# MLS01-TG000-C08.net
KiCad netlist of a schematic drawn in EAGLE
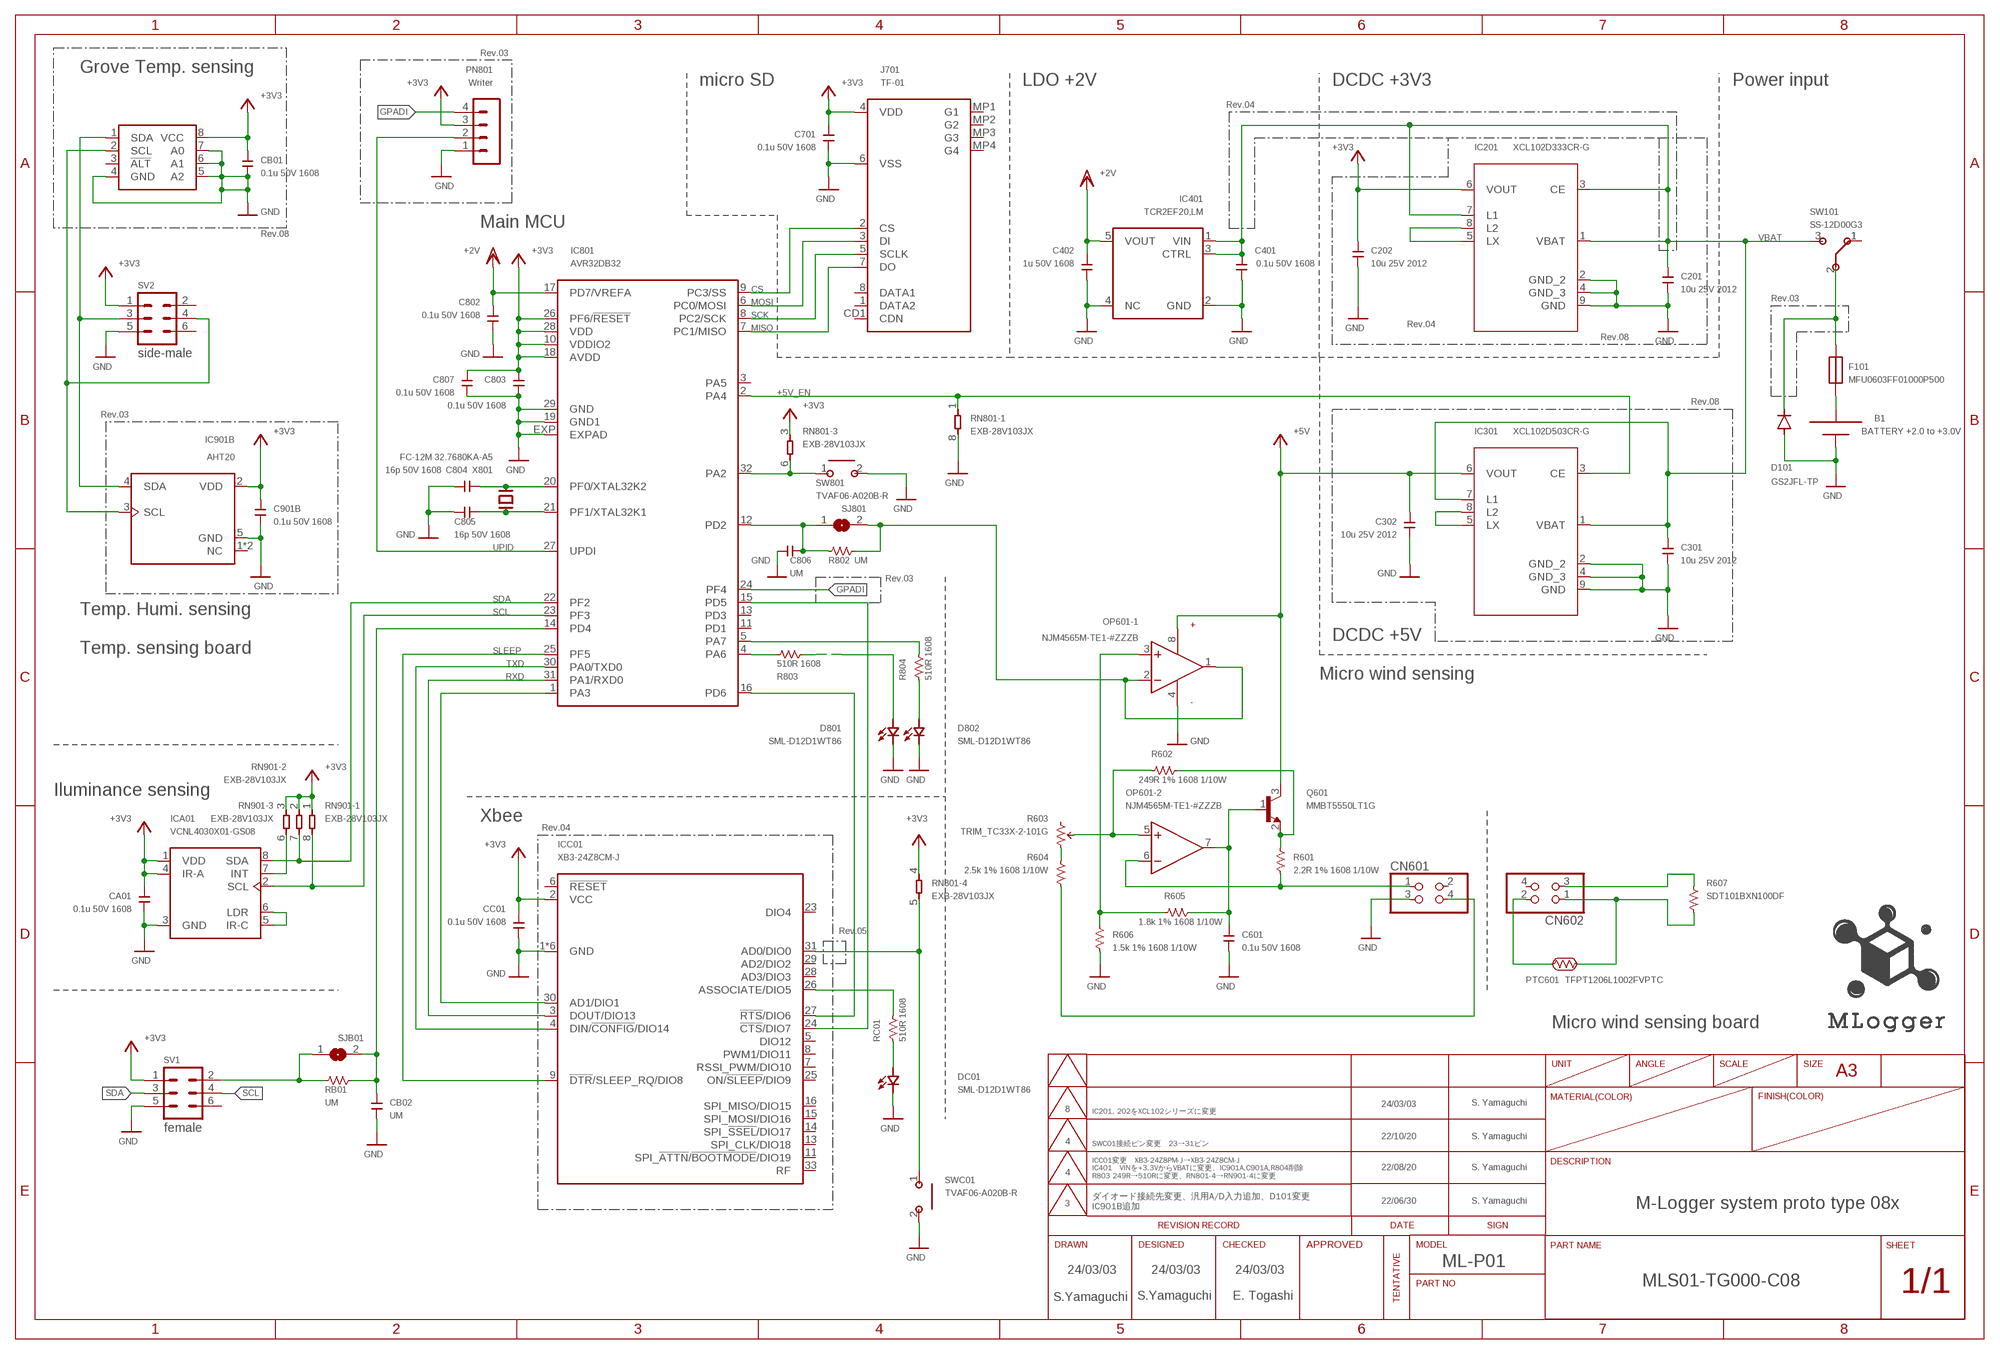
[diagram p0: schematic, sheet 1]

(export (version "E")
  (design (tool "Eeschema 10.0.6"))
  (components
    (comp (ref "B1")
      (value "BATTERY +2.0 to +3.0V")
      (footprint "eagle-import:PAD")
      (libsource (lib "eagle-import") (part "BATTERY"))
    )
    (comp (ref "C201")
      (value "10u 25V 2012")
      (footprint "eagle-import:C-2012_0805")
      (libsource (lib "eagle-import") (part "CL21B105KBFNNNG"))
    )
    (comp (ref "C202")
      (value "10u 25V 2012")
      (footprint "eagle-import:C-2012_0805")
      (libsource (lib "eagle-import") (part "CL21B105KBFNNNG"))
    )
    (comp (ref "C301")
      (value "10u 25V 2012")
      (footprint "eagle-import:C-2012_0805")
      (libsource (lib "eagle-import") (part "CL21B105KBFNNNG"))
    )
    (comp (ref "C302")
      (value "10u 25V 2012")
      (footprint "eagle-import:C-2012_0805")
      (libsource (lib "eagle-import") (part "CL21B105KBFNNNG"))
    )
    (comp (ref "C401")
      (value "0.1u 50V 1608")
      (footprint "eagle-import:C-1608_0603")
      (libsource (lib "eagle-import") (part "CL10A105KP8NNNC"))
    )
    (comp (ref "C402")
      (value "1u 50V 1608")
      (footprint "eagle-import:C-1608_0603")
      (libsource (lib "eagle-import") (part "CL10A105KP8NNNC"))
    )
    (comp (ref "C601")
      (value "0.1u 50V 1608")
      (footprint "eagle-import:C-1608_0603")
      (libsource (lib "eagle-import") (part "CL10A105KP8NNNC"))
    )
    (comp (ref "C701")
      (value "0.1u 50V 1608")
      (footprint "eagle-import:C-1608_0603")
      (libsource (lib "eagle-import") (part "CL10A105KP8NNNC"))
    )
    (comp (ref "C802")
      (value "0.1u 50V 1608")
      (footprint "eagle-import:C-1608_0603")
      (libsource (lib "eagle-import") (part "CL10A105KP8NNNC"))
    )
    (comp (ref "C803")
      (value "0.1u 50V 1608")
      (footprint "eagle-import:C-1608_0603")
      (libsource (lib "eagle-import") (part "CL10A105KP8NNNC"))
    )
    (comp (ref "C804")
      (value "16p 50V 1608")
      (footprint "eagle-import:C-1608_0603")
      (libsource (lib "eagle-import") (part "CL10A105KP8NNNC"))
    )
    (comp (ref "C805")
      (value "16p 50V 1608")
      (footprint "eagle-import:C-1608_0603")
      (libsource (lib "eagle-import") (part "CL10A105KP8NNNC"))
    )
    (comp (ref "C806")
      (value "UM")
      (footprint "eagle-import:C-1608_0603")
      (libsource (lib "eagle-import") (part "CL10A105KP8NNNC"))
    )
    (comp (ref "C807")
      (value "0.1u 50V 1608")
      (footprint "eagle-import:C-1608_0603")
      (libsource (lib "eagle-import") (part "CL10A105KP8NNNC"))
    )
    (comp (ref "C901B")
      (value "0.1u 50V 1608")
      (footprint "eagle-import:C-1608_0603")
      (libsource (lib "eagle-import") (part "CL10A105KP8NNNC"))
    )
    (comp (ref "CA01")
      (value "0.1u 50V 1608")
      (footprint "eagle-import:C-1608_0603")
      (libsource (lib "eagle-import") (part "CL10A105KP8NNNC"))
    )
    (comp (ref "CB01")
      (value "0.1u 50V 1608")
      (footprint "eagle-import:C-1608_0603")
      (libsource (lib "eagle-import") (part "CL10A105KP8NNNC"))
    )
    (comp (ref "CB02")
      (value "UM")
      (footprint "eagle-import:C-1608_0603")
      (libsource (lib "eagle-import") (part "CL10A105KP8NNNC"))
    )
    (comp (ref "CC01")
      (value "0.1u 50V 1608")
      (footprint "eagle-import:C-1608_0603")
      (libsource (lib "eagle-import") (part "CL10A105KP8NNNC"))
    )
    (comp (ref "CN601")
      (value "PINHD-2X2")
      (footprint "eagle-import:2X02")
      (libsource (lib "eagle-import") (part "PINHD-2X2"))
    )
    (comp (ref "CN602")
      (value "PINHD-2X2/90")
      (footprint "eagle-import:2X02_90")
      (libsource (lib "eagle-import") (part "PINHD-2X2/90"))
    )
    (comp (ref "D101")
      (value "GS2JFL-TP")
      (footprint "eagle-import:SODFL5629X125N")
      (libsource (lib "eagle-import") (part "GS2JFL-TP"))
    )
    (comp (ref "D801")
      (value "SML-D12D1WT86")
      (footprint "eagle-import:SMD-1608")
      (libsource (lib "eagle-import") (part "SML-D12D1WT86"))
    )
    (comp (ref "D802")
      (value "SML-D12D1WT86")
      (footprint "eagle-import:SMD-1608")
      (libsource (lib "eagle-import") (part "SML-D12D1WT86"))
    )
    (comp (ref "DC01")
      (value "SML-D12D1WT86")
      (footprint "eagle-import:SMD-1608")
      (libsource (lib "eagle-import") (part "SML-D12D1WT86"))
    )
    (comp (ref "F101")
      (value "MFU0603FF01000P500")
      (footprint "eagle-import:FUSC1608X60N")
      (libsource (lib "eagle-import") (part "MFU0603FF01000P500"))
    )
    (comp (ref "IC201")
      (value "XCL102D333CR-G")
      (footprint "eagle-import:CL-2025-02_TOR")
      (fields
        (field (name "MANUFACTURER_PART_NUMBER") "XCL102D503CR-G")
        (field (name "COPYRIGHT") "Copyright (C) 2021 Accelerated Designs. All rights reserved")
      )
      (libsource (lib "eagle-import") (part "XCL102D503CR-GCL-2025-02_TOR"))
    )
    (comp (ref "IC301")
      (value "XCL102D503CR-G")
      (footprint "eagle-import:CL-2025-02_TOR")
      (fields (field (name "COPYRIGHT") "Copyright (C) 2021 Accelerated Designs. All rights reserved"))
      (libsource (lib "eagle-import") (part "XCL102D503CR-GCL-2025-02_TOR"))
    )
    (comp (ref "IC401")
      (value "TCR2EF20,LM")
      (footprint "eagle-import:SOT23-5L")
      (libsource (lib "eagle-import") (part "TCR2EF20,LM"))
    )
    (comp (ref "IC801")
      (value "AVR32DB32")
      (footprint "eagle-import:HVQFN32")
      (libsource (lib "eagle-import") (part "AVR32DB32"))
    )
    (comp (ref "IC901B")
      (value "AHT20")
      (footprint "eagle-import:PSON100P300X300X110-6N")
      (fields (field (name "MF") "Asair"))
      (libsource (lib "eagle-import") (part "AHT20"))
    )
    (comp (ref "ICA01")
      (value "VCNL4030X01-GS08")
      (footprint "eagle-import:VISHAY_VCNL4030X01-GS08")
      (fields (field (name "MF") "Vishay"))
      (libsource (lib "eagle-import") (part "VCNL4030X01-GS08"))
    )
    (comp (ref "ICC01")
      (value "XB3-24Z8CM-J")
      (footprint "eagle-import:XCVR_XB3-24Z8CM-J")
      (fields (field (name "MF") "Digi International"))
      (libsource (lib "eagle-import") (part "XB3-24Z8CM-J"))
    )
    (comp (ref "J701")
      (value "TF-01")
      (footprint "eagle-import:TF-01A")
      (libsource (lib "eagle-import") (part "TF-01"))
    )
    (comp (ref "OP601")
      (value "NJM4565M-TE1-#ZZZB")
      (footprint "eagle-import:SOIC127P680X175-8N")
      (libsource (lib "eagle-import") (part "NJM4565M-TE1-#ZZZB"))
    )
    (comp (ref "PN801")
      (value "Writer")
      (footprint "eagle-import:MA04-1")
      (libsource (lib "eagle-import") (part "MA04-1"))
    )
    (comp (ref "PTC601")
      (value "TFPT1206L1002FVPTC")
      (footprint "eagle-import:C1206")
      (libsource (lib "eagle-import") (part "TFPT1206L1002FVPTC"))
    )
    (comp (ref "Q601")
      (value "MMBT5550LT1G")
      (footprint "eagle-import:SOT95P237X111-3N")
      (libsource (lib "eagle-import") (part "MMBT5550LT1G"))
    )
    (comp (ref "R601")
      (value "2.2R 1% 1608 1/10W")
      (footprint "eagle-import:R-1608_0603")
      (libsource (lib "eagle-import") (part "R-1608"))
    )
    (comp (ref "R602")
      (value "249R 1% 1608 1/10W")
      (footprint "eagle-import:R-1608_0603")
      (libsource (lib "eagle-import") (part "R-1608"))
    )
    (comp (ref "R603")
      (value "TRIM_TC33X-2-101G")
      (footprint "eagle-import:TRIM_TC33X-2-101G")
      (libsource (lib "eagle-import") (part "TRIM_TC33X-2-101G"))
    )
    (comp (ref "R604")
      (value "2.5k 1% 1608 1/10W")
      (footprint "eagle-import:R-1608_0603")
      (libsource (lib "eagle-import") (part "R-1608"))
    )
    (comp (ref "R605")
      (value "1.8k 1% 1608 1/10W")
      (footprint "eagle-import:R-1608_0603")
      (libsource (lib "eagle-import") (part "R-1608"))
    )
    (comp (ref "R606")
      (value "1.5k 1% 1608 1/10W")
      (footprint "eagle-import:R-1608_0603")
      (libsource (lib "eagle-import") (part "R-1608"))
    )
    (comp (ref "R607")
      (value "SDT101BXN100DF")
      (footprint "eagle-import:SDT101BXN100DF")
      (libsource (lib "eagle-import") (part "SDT101BXN100DF"))
    )
    (comp (ref "R802")
      (value "UM")
      (footprint "eagle-import:R-1608_0603")
      (libsource (lib "eagle-import") (part "R-1608"))
    )
    (comp (ref "R803")
      (value "510R 1608")
      (footprint "eagle-import:R-1608_0603")
      (libsource (lib "eagle-import") (part "R-1608"))
    )
    (comp (ref "R804")
      (value "510R 1608")
      (footprint "eagle-import:R-1608_0603")
      (libsource (lib "eagle-import") (part "R-1608"))
    )
    (comp (ref "RB01")
      (value "UM")
      (footprint "eagle-import:R-1608_0603")
      (libsource (lib "eagle-import") (part "R-1608"))
    )
    (comp (ref "RC01")
      (value "510R 1608")
      (footprint "eagle-import:R-1608_0603")
      (libsource (lib "eagle-import") (part "R-1608"))
    )
    (comp (ref "RN801")
      (value "EXB-28V103JX")
      (footprint "eagle-import:RESCAXS50P200X100X45-8N")
      (libsource (lib "eagle-import") (part "EXB-28V103JX"))
    )
    (comp (ref "RN901")
      (value "EXB-28V103JX")
      (footprint "eagle-import:RESCAXS50P200X100X45-8N")
      (libsource (lib "eagle-import") (part "EXB-28V103JX"))
    )
    (comp (ref "SJ801")
      (value "SJ")
      (footprint "eagle-import:SJ")
      (libsource (lib "eagle-import") (part "SJ"))
    )
    (comp (ref "SJB01")
      (value "SJ")
      (footprint "eagle-import:SJ")
      (libsource (lib "eagle-import") (part "SJ"))
    )
    (comp (ref "SV1")
      (value "female")
      (footprint "eagle-import:MA03-2-FEMALE")
      (libsource (lib "eagle-import") (part "MA03-2-FEMALE"))
    )
    (comp (ref "SV2")
      (value "side-male")
      (footprint "eagle-import:MA03-2-SIDE-MALE")
      (libsource (lib "eagle-import") (part "MA03-2-SIDE-MALE"))
    )
    (comp (ref "SW101")
      (value "SS-12D00G3")
      (footprint "eagle-import:SS-12D00G3")
      (libsource (lib "eagle-import") (part "SS-12D00G3"))
    )
    (comp (ref "SW801")
      (value "TVAF06-A020B-R")
      (footprint "eagle-import:TVAF06-A020B-R")
      (libsource (lib "eagle-import") (part "TVAF06-A020B-R"))
    )
    (comp (ref "SWC01")
      (value "TVAF06-A020B-R")
      (footprint "eagle-import:TVAF06-A020B-R")
      (libsource (lib "eagle-import") (part "TVAF06-A020B-R"))
    )
    (comp (ref "U$4")
      (value "P3T1570DP")
      (footprint "eagle-import:TSSOP8")
      (libsource (lib "eagle-import") (part "P3T1570DP"))
    )
    (comp (ref "X801")
      (value "FC-12M 32.7680KA-A5")
      (footprint "eagle-import:X2-SMD-L2.0X1.2X0.55MM")
      (fields (field (name "MF") "EPSON") (field (name "MP") "FC-12M"))
      (libsource (lib "eagle-import") (part "SMD-CRYSTAL-32.768KHZ-12.5PF-20PPM-90K(2P-L2.0X1.2MM)"))
    )
  )
  (nets
    (net (code "1") (name "+2V") (class "Default")
      (node (ref "C402") (pin "P$1") (pinfunction "1_P$1") (pintype "passive"))
      (node (ref "C802") (pin "P$1") (pinfunction "1_P$1") (pintype "passive"))
      (node (ref "IC401") (pin "5") (pinfunction "VOUT_5") (pintype "bidirectional"))
      (node (ref "IC801") (pin "17") (pinfunction "PD7/VREFA_17") (pintype "bidirectional"))
    )
    (net (code "2") (name "+3V3") (class "Default")
      (node (ref "C202") (pin "P$2") (pinfunction "2_P$2") (pintype "passive"))
      (node (ref "C701") (pin "P$1") (pinfunction "1_P$1") (pintype "passive"))
      (node (ref "C803") (pin "P$1") (pinfunction "1_P$1") (pintype "passive"))
      (node (ref "C807") (pin "P$1") (pinfunction "1_P$1") (pintype "passive"))
      (node (ref "C901B") (pin "P$1") (pinfunction "1_P$1") (pintype "passive"))
      (node (ref "CA01") (pin "P$1") (pinfunction "1_P$1") (pintype "passive"))
      (node (ref "CB01") (pin "P$1") (pinfunction "1_P$1") (pintype "passive"))
      (node (ref "CC01") (pin "P$1") (pinfunction "1_P$1") (pintype "passive"))
      (node (ref "IC201") (pin "6") (pinfunction "VOUT_6") (pintype "output"))
      (node (ref "IC801") (pin "10") (pinfunction "VDDIO2_10") (pintype "bidirectional"))
      (node (ref "IC801") (pin "18") (pinfunction "AVDD_18") (pintype "bidirectional"))
      (node (ref "IC801") (pin "26") (pinfunction "PF6/~{RESET}_26") (pintype "bidirectional"))
      (node (ref "IC801") (pin "28") (pinfunction "VDD_28") (pintype "bidirectional"))
      (node (ref "IC901B") (pin "2") (pinfunction "VDD_2") (pintype "power_in"))
      (node (ref "ICA01") (pin "1") (pinfunction "VDD_1") (pintype "power_in"))
      (node (ref "ICA01") (pin "4") (pinfunction "IR-A_4") (pintype "input"))
      (node (ref "ICC01") (pin "2") (pinfunction "VCC_2") (pintype "power_in"))
      (node (ref "J701") (pin "4") (pinfunction "VDD_4") (pintype "bidirectional"))
      (node (ref "PN801") (pin "3") (pinfunction "3_3") (pintype "passive"))
      (node (ref "RN801") (pin "3") (pinfunction "1_3") (pintype "passive"))
      (node (ref "RN801") (pin "4") (pinfunction "1_4") (pintype "passive"))
      (node (ref "RN901") (pin "1") (pinfunction "1_1") (pintype "passive"))
      (node (ref "RN901") (pin "2") (pinfunction "1_2") (pintype "passive"))
      (node (ref "RN901") (pin "3") (pinfunction "1_3") (pintype "passive"))
      (node (ref "SV1") (pin "1") (pinfunction "1_1") (pintype "passive"))
      (node (ref "SV2") (pin "1") (pinfunction "1_1") (pintype "passive"))
      (node (ref "U$4") (pin "8") (pinfunction "VCC_8") (pintype "bidirectional"))
    )
    (net (code "3") (name "+5V") (class "Default")
      (node (ref "C302") (pin "P$2") (pinfunction "2_P$2") (pintype "passive"))
      (node (ref "IC301") (pin "6") (pinfunction "VOUT_6") (pintype "output"))
      (node (ref "OP601") (pin "8") (pinfunction "V+_8") (pintype "power_in"))
      (node (ref "Q601") (pin "3") (pinfunction "C_3") (pintype "passive"))
    )
    (net (code "4") (name "/+5V_EN") (class "Default")
      (node (ref "IC301") (pin "3") (pinfunction "CE_3") (pintype "input"))
      (node (ref "IC801") (pin "2") (pinfunction "PA4_2") (pintype "bidirectional"))
      (node (ref "RN801") (pin "1") (pinfunction "1_1") (pintype "passive"))
    )
    (net (code "5") (name "/CS") (class "Default")
      (node (ref "IC801") (pin "9") (pinfunction "PC3/SS_9") (pintype "bidirectional"))
      (node (ref "J701") (pin "2") (pinfunction "CS_2") (pintype "bidirectional"))
    )
    (net (code "6") (name "/MISO") (class "Default")
      (node (ref "IC801") (pin "7") (pinfunction "PC1/MISO_7") (pintype "bidirectional"))
      (node (ref "J701") (pin "7") (pinfunction "DO_7") (pintype "bidirectional"))
    )
    (net (code "7") (name "/MOSI") (class "Default")
      (node (ref "IC801") (pin "6") (pinfunction "PC0/MOSI_6") (pintype "bidirectional"))
      (node (ref "J701") (pin "3") (pinfunction "DI_3") (pintype "bidirectional"))
    )
    (net (code "8") (name "/RXD") (class "Default")
      (node (ref "IC801") (pin "31") (pinfunction "PA1/RXD0_31") (pintype "bidirectional"))
      (node (ref "ICC01") (pin "3") (pinfunction "DOUT/DIO13_3") (pintype "bidirectional"))
    )
    (net (code "9") (name "/SCK") (class "Default")
      (node (ref "IC801") (pin "8") (pinfunction "PC2/SCK_8") (pintype "bidirectional"))
      (node (ref "J701") (pin "5") (pinfunction "SCLK_5") (pintype "bidirectional"))
    )
    (net (code "10") (name "/SLEEP") (class "Default")
      (node (ref "IC801") (pin "25") (pinfunction "PF5_25") (pintype "bidirectional"))
      (node (ref "ICC01") (pin "9") (pinfunction "~{DTR}/SLEEP_RQ/DIO8_9") (pintype "bidirectional"))
    )
    (net (code "11") (name "/TXD") (class "Default")
      (node (ref "IC801") (pin "30") (pinfunction "PA0/TXD0_30") (pintype "bidirectional"))
      (node (ref "ICC01") (pin "4") (pinfunction "DIN/~{CONFIG}/DIO14_4") (pintype "bidirectional"))
    )
    (net (code "12") (name "/UPID") (class "Default")
      (node (ref "IC801") (pin "27") (pinfunction "UPDI_27") (pintype "bidirectional"))
      (node (ref "PN801") (pin "2") (pinfunction "2_2") (pintype "passive"))
    )
    (net (code "13") (name "/VBAT") (class "Default")
      (node (ref "C201") (pin "P$2") (pinfunction "2_P$2") (pintype "passive"))
      (node (ref "C301") (pin "P$2") (pinfunction "2_P$2") (pintype "passive"))
      (node (ref "C401") (pin "P$1") (pinfunction "1_P$1") (pintype "passive"))
      (node (ref "IC201") (pin "1") (pinfunction "VBAT_1") (pintype "power_in"))
      (node (ref "IC201") (pin "3") (pinfunction "CE_3") (pintype "input"))
      (node (ref "IC201") (pin "7") (pinfunction "L1_7") (pintype "bidirectional"))
      (node (ref "IC301") (pin "1") (pinfunction "VBAT_1") (pintype "power_in"))
      (node (ref "IC301") (pin "7") (pinfunction "L1_7") (pintype "bidirectional"))
      (node (ref "IC401") (pin "1") (pinfunction "VIN_1") (pintype "bidirectional"))
      (node (ref "IC401") (pin "3") (pinfunction "CTRL_3") (pintype "bidirectional"))
      (node (ref "SW101") (pin "3") (pinfunction "2_3") (pintype "bidirectional"))
    )
    (net (code "14") (name "GND") (class "Default")
      (node (ref "B1") (pin "2") (pinfunction "-_2") (pintype "bidirectional"))
      (node (ref "C201") (pin "P$1") (pinfunction "1_P$1") (pintype "passive"))
      (node (ref "C202") (pin "P$1") (pinfunction "1_P$1") (pintype "passive"))
      (node (ref "C301") (pin "P$1") (pinfunction "1_P$1") (pintype "passive"))
      (node (ref "C302") (pin "P$1") (pinfunction "1_P$1") (pintype "passive"))
      (node (ref "C401") (pin "P$2") (pinfunction "2_P$2") (pintype "passive"))
      (node (ref "C402") (pin "P$2") (pinfunction "2_P$2") (pintype "passive"))
      (node (ref "C601") (pin "P$2") (pinfunction "2_P$2") (pintype "passive"))
      (node (ref "C701") (pin "P$2") (pinfunction "2_P$2") (pintype "passive"))
      (node (ref "C802") (pin "P$2") (pinfunction "2_P$2") (pintype "passive"))
      (node (ref "C803") (pin "P$2") (pinfunction "2_P$2") (pintype "passive"))
      (node (ref "C804") (pin "P$2") (pinfunction "2_P$2") (pintype "passive"))
      (node (ref "C805") (pin "P$2") (pinfunction "2_P$2") (pintype "passive"))
      (node (ref "C806") (pin "P$2") (pinfunction "2_P$2") (pintype "passive"))
      (node (ref "C807") (pin "P$2") (pinfunction "2_P$2") (pintype "passive"))
      (node (ref "C901B") (pin "P$2") (pinfunction "2_P$2") (pintype "passive"))
      (node (ref "CA01") (pin "P$2") (pinfunction "2_P$2") (pintype "passive"))
      (node (ref "CB01") (pin "P$2") (pinfunction "2_P$2") (pintype "passive"))
      (node (ref "CB02") (pin "P$2") (pinfunction "2_P$2") (pintype "passive"))
      (node (ref "CC01") (pin "P$2") (pinfunction "2_P$2") (pintype "passive"))
      (node (ref "CN601") (pin "3") (pinfunction "3_3") (pintype "passive"))
      (node (ref "D101") (pin "2") (pinfunction "A_2") (pintype "passive"))
      (node (ref "D801") (pin "2") (pinfunction "C_2") (pintype "passive"))
      (node (ref "D802") (pin "2") (pinfunction "C_2") (pintype "passive"))
      (node (ref "DC01") (pin "2") (pinfunction "C_2") (pintype "passive"))
      (node (ref "IC201") (pin "2") (pinfunction "GND_2_2") (pintype "passive"))
      (node (ref "IC201") (pin "4") (pinfunction "GND_3_4") (pintype "passive"))
      (node (ref "IC201") (pin "9") (pinfunction "GND_9") (pintype "passive"))
      (node (ref "IC301") (pin "2") (pinfunction "GND_2_2") (pintype "passive"))
      (node (ref "IC301") (pin "4") (pinfunction "GND_3_4") (pintype "passive"))
      (node (ref "IC301") (pin "9") (pinfunction "GND_9") (pintype "passive"))
      (node (ref "IC401") (pin "2") (pinfunction "GND_2") (pintype "bidirectional"))
      (node (ref "IC401") (pin "4") (pinfunction "NC_4") (pintype "bidirectional"))
      (node (ref "IC801") (pin "19") (pinfunction "GND1_19") (pintype "bidirectional"))
      (node (ref "IC801") (pin "29") (pinfunction "GND_29") (pintype "bidirectional"))
      (node (ref "IC801") (pin "EXP") (pinfunction "EXPAD_EXP") (pintype "bidirectional"))
      (node (ref "IC901B") (pin "5") (pinfunction "GND_5") (pintype "power_in"))
      (node (ref "ICA01") (pin "3") (pinfunction "GND_3") (pintype "power_in"))
      (node (ref "ICC01") (pin "1") (pinfunction "GND_1") (pintype "power_in"))
      (node (ref "ICC01") (pin "10") (pinfunction "GND_10") (pintype "power_in"))
      (node (ref "ICC01") (pin "12") (pinfunction "GND_12") (pintype "power_in"))
      (node (ref "ICC01") (pin "21") (pinfunction "GND_21") (pintype "power_in"))
      (node (ref "ICC01") (pin "32") (pinfunction "GND_32") (pintype "power_in"))
      (node (ref "ICC01") (pin "34") (pinfunction "GND_34") (pintype "power_in"))
      (node (ref "J701") (pin "6") (pinfunction "VSS_6") (pintype "bidirectional"))
      (node (ref "OP601") (pin "4") (pinfunction "V-_4") (pintype "power_in"))
      (node (ref "PN801") (pin "1") (pinfunction "1_1") (pintype "passive"))
      (node (ref "R606") (pin "1") (pinfunction "1_1") (pintype "passive"))
      (node (ref "RN801") (pin "8") (pinfunction "2_8") (pintype "passive"))
      (node (ref "SV1") (pin "5") (pinfunction "5_5") (pintype "passive"))
      (node (ref "SV2") (pin "5") (pinfunction "5_5") (pintype "passive"))
      (node (ref "SW801") (pin "2") (pinfunction "2_2") (pintype "bidirectional"))
      (node (ref "SWC01") (pin "2") (pinfunction "2_2") (pintype "bidirectional"))
      (node (ref "U$4") (pin "4") (pinfunction "GND_4") (pintype "bidirectional"))
      (node (ref "U$4") (pin "5") (pinfunction "A2_5") (pintype "bidirectional"))
      (node (ref "U$4") (pin "6") (pinfunction "A1_6") (pintype "bidirectional"))
      (node (ref "U$4") (pin "7") (pinfunction "A0_7") (pintype "bidirectional"))
    )
    (net (code "15") (name "GPADI") (class "Default")
      (node (ref "IC801") (pin "24") (pinfunction "PF4_24") (pintype "bidirectional"))
      (node (ref "PN801") (pin "4") (pinfunction "4_4") (pintype "passive"))
    )
    (net (code "16") (name "Net-(B1-+)") (class "Default")
      (node (ref "B1") (pin "1") (pinfunction "+_1") (pintype "bidirectional"))
      (node (ref "F101") (pin "1") (pinfunction "1_1") (pintype "bidirectional"))
    )
    (net (code "17") (name "Net-(C601-1)") (class "Default")
      (node (ref "C601") (pin "P$1") (pinfunction "1_P$1") (pintype "passive"))
      (node (ref "OP601") (pin "7") (pinfunction "OUT_7") (pintype "output"))
      (node (ref "Q601") (pin "1") (pinfunction "B_1") (pintype "passive"))
      (node (ref "R605") (pin "2") (pinfunction "2_2") (pintype "passive"))
    )
    (net (code "18") (name "Net-(C804-1)") (class "Default")
      (node (ref "C804") (pin "P$1") (pinfunction "1_P$1") (pintype "passive"))
      (node (ref "IC801") (pin "20") (pinfunction "PF0/XTAL32K2_20") (pintype "bidirectional"))
      (node (ref "X801") (pin "1") (pinfunction "1_1") (pintype "passive"))
    )
    (net (code "19") (name "Net-(C805-1)") (class "Default")
      (node (ref "C805") (pin "P$1") (pinfunction "1_P$1") (pintype "passive"))
      (node (ref "IC801") (pin "21") (pinfunction "PF1/XTAL32K1_21") (pintype "bidirectional"))
      (node (ref "X801") (pin "2") (pinfunction "2_2") (pintype "passive"))
    )
    (net (code "20") (name "Net-(C806-1)") (class "Default")
      (node (ref "C806") (pin "P$1") (pinfunction "1_P$1") (pintype "passive"))
      (node (ref "IC801") (pin "12") (pinfunction "PD2_12") (pintype "bidirectional"))
      (node (ref "R802") (pin "1") (pinfunction "1_1") (pintype "passive"))
      (node (ref "SJ801") (pin "1") (pinfunction "1_1") (pintype "passive"))
    )
    (net (code "21") (name "Net-(CB02-1)") (class "Default")
      (node (ref "CB02") (pin "P$1") (pinfunction "1_P$1") (pintype "passive"))
      (node (ref "IC801") (pin "14") (pinfunction "PD4_14") (pintype "bidirectional"))
      (node (ref "RB01") (pin "2") (pinfunction "2_2") (pintype "passive"))
      (node (ref "SJB01") (pin "2") (pinfunction "2_2") (pintype "passive"))
    )
    (net (code "22") (name "Net-(CN601-Pad4)") (class "Default")
      (node (ref "CN601") (pin "4") (pinfunction "4_4") (pintype "passive"))
      (node (ref "R604") (pin "1") (pinfunction "1_1") (pintype "passive"))
    )
    (net (code "23") (name "Net-(CN602-Pad1)") (class "Default")
      (node (ref "CN602") (pin "1") (pinfunction "1_1") (pintype "passive"))
      (node (ref "PTC601") (pin "1") (pinfunction "1_1") (pintype "passive"))
      (node (ref "R607") (pin "1") (pinfunction "1_1") (pintype "passive"))
    )
    (net (code "24") (name "Net-(CN602-Pad2)") (class "Default")
      (node (ref "CN602") (pin "2") (pinfunction "2_2") (pintype "passive"))
      (node (ref "PTC601") (pin "2") (pinfunction "2_2") (pintype "passive"))
    )
    (net (code "25") (name "Net-(CN602-Pad3)") (class "Default")
      (node (ref "CN602") (pin "3") (pinfunction "3_3") (pintype "passive"))
      (node (ref "R607") (pin "2") (pinfunction "2_2") (pintype "passive"))
    )
    (net (code "26") (name "Net-(D101-C)") (class "Default")
      (node (ref "D101") (pin "1") (pinfunction "C_1") (pintype "passive"))
      (node (ref "F101") (pin "2") (pinfunction "2_2") (pintype "bidirectional"))
      (node (ref "SW101") (pin "2") (pinfunction "P$1_2") (pintype "bidirectional"))
    )
    (net (code "27") (name "Net-(D801-A)") (class "Default")
      (node (ref "D801") (pin "1") (pinfunction "A_1") (pintype "passive"))
      (node (ref "R803") (pin "2") (pinfunction "2_2") (pintype "passive"))
    )
    (net (code "28") (name "Net-(D802-A)") (class "Default")
      (node (ref "D802") (pin "1") (pinfunction "A_1") (pintype "passive"))
      (node (ref "R804") (pin "1") (pinfunction "1_1") (pintype "passive"))
    )
    (net (code "29") (name "Net-(DC01-A)") (class "Default")
      (node (ref "DC01") (pin "1") (pinfunction "A_1") (pintype "passive"))
      (node (ref "RC01") (pin "1") (pinfunction "1_1") (pintype "passive"))
    )
    (net (code "30") (name "Net-(IC201-L2)") (class "Default")
      (node (ref "IC201") (pin "5") (pinfunction "LX_5") (pintype "passive"))
      (node (ref "IC201") (pin "8") (pinfunction "L2_8") (pintype "bidirectional"))
    )
    (net (code "31") (name "Net-(IC301-L2)") (class "Default")
      (node (ref "IC301") (pin "5") (pinfunction "LX_5") (pintype "passive"))
      (node (ref "IC301") (pin "8") (pinfunction "L2_8") (pintype "bidirectional"))
    )
    (net (code "32") (name "Net-(IC801-PA2)") (class "Default")
      (node (ref "IC801") (pin "32") (pinfunction "PA2_32") (pintype "bidirectional"))
      (node (ref "RN801") (pin "6") (pinfunction "2_6") (pintype "passive"))
      (node (ref "SW801") (pin "1") (pinfunction "1_1") (pintype "bidirectional"))
    )
    (net (code "33") (name "Net-(IC801-PA3)") (class "Default")
      (node (ref "IC801") (pin "1") (pinfunction "PA3_1") (pintype "bidirectional"))
      (node (ref "ICC01") (pin "30") (pinfunction "AD1/DIO1_30") (pintype "bidirectional"))
    )
    (net (code "34") (name "Net-(IC801-PA6)") (class "Default")
      (node (ref "IC801") (pin "4") (pinfunction "PA6_4") (pintype "bidirectional"))
      (node (ref "R803") (pin "1") (pinfunction "1_1") (pintype "passive"))
    )
    (net (code "35") (name "Net-(IC801-PA7)") (class "Default")
      (node (ref "IC801") (pin "5") (pinfunction "PA7_5") (pintype "bidirectional"))
      (node (ref "R804") (pin "2") (pinfunction "2_2") (pintype "passive"))
    )
    (net (code "36") (name "Net-(IC801-PD5)") (class "Default")
      (node (ref "IC801") (pin "15") (pinfunction "PD5_15") (pintype "bidirectional"))
      (node (ref "ICC01") (pin "24") (pinfunction "~{CTS}/DIO7_24") (pintype "bidirectional"))
    )
    (net (code "37") (name "Net-(IC801-PD6)") (class "Default")
      (node (ref "IC801") (pin "16") (pinfunction "PD6_16") (pintype "bidirectional"))
      (node (ref "ICC01") (pin "27") (pinfunction "~{RTS}/DIO6_27") (pintype "bidirectional"))
    )
    (net (code "38") (name "Net-(ICA01-INT)") (class "Default")
      (node (ref "ICA01") (pin "7") (pinfunction "INT_7") (pintype "bidirectional"))
      (node (ref "RN901") (pin "6") (pinfunction "2_6") (pintype "passive"))
    )
    (net (code "39") (name "Net-(ICA01-IR-C)") (class "Default")
      (node (ref "ICA01") (pin "5") (pinfunction "IR-C_5") (pintype "output"))
      (node (ref "ICA01") (pin "6") (pinfunction "LDR_6") (pintype "bidirectional"))
    )
    (net (code "40") (name "Net-(ICC01-AD0{slash}DIO0)") (class "Default")
      (node (ref "ICC01") (pin "31") (pinfunction "AD0/DIO0_31") (pintype "bidirectional"))
      (node (ref "RN801") (pin "5") (pinfunction "2_5") (pintype "passive"))
      (node (ref "SWC01") (pin "1") (pinfunction "1_1") (pintype "bidirectional"))
    )
    (net (code "41") (name "Net-(ICC01-ASSOCIATE{slash}DIO5)") (class "Default")
      (node (ref "ICC01") (pin "26") (pinfunction "ASSOCIATE/DIO5_26") (pintype "bidirectional"))
      (node (ref "RC01") (pin "2") (pinfunction "2_2") (pintype "passive"))
    )
    (net (code "42") (name "Net-(OP601A-+IN)") (class "Default")
      (node (ref "OP601") (pin "3") (pinfunction "+IN_3") (pintype "input"))
      (node (ref "R605") (pin "1") (pinfunction "1_1") (pintype "passive"))
      (node (ref "R606") (pin "2") (pinfunction "2_2") (pintype "passive"))
    )
    (net (code "43") (name "Net-(OP601A--IN)") (class "Default")
      (node (ref "OP601") (pin "1") (pinfunction "OUT_1") (pintype "output"))
      (node (ref "OP601") (pin "2") (pinfunction "-IN_2") (pintype "input"))
      (node (ref "R802") (pin "2") (pinfunction "2_2") (pintype "passive"))
      (node (ref "SJ801") (pin "2") (pinfunction "2_2") (pintype "passive"))
    )
    (net (code "44") (name "Net-(OP601B-+IN)") (class "Default")
      (node (ref "OP601") (pin "5") (pinfunction "+IN_5") (pintype "input"))
      (node (ref "R602") (pin "1") (pinfunction "1_1") (pintype "passive"))
      (node (ref "R603") (pin "2") (pinfunction "2_2") (pintype "bidirectional"))
    )
    (net (code "45") (name "Net-(OP601B--IN)") (class "Default")
      (node (ref "CN601") (pin "1") (pinfunction "1_1") (pintype "passive"))
      (node (ref "OP601") (pin "6") (pinfunction "-IN_6") (pintype "input"))
      (node (ref "R601") (pin "1") (pinfunction "1_1") (pintype "passive"))
    )
    (net (code "46") (name "Net-(Q601-E)") (class "Default")
      (node (ref "Q601") (pin "2") (pinfunction "E_2") (pintype "passive"))
      (node (ref "R601") (pin "2") (pinfunction "2_2") (pintype "passive"))
      (node (ref "R602") (pin "2") (pinfunction "2_2") (pintype "passive"))
    )
    (net (code "47") (name "Net-(R603-Pad3)") (class "Default")
      (node (ref "R603") (pin "3") (pinfunction "3_3") (pintype "passive"))
      (node (ref "R604") (pin "2") (pinfunction "2_2") (pintype "passive"))
    )
    (net (code "48") (name "Net-(RB01-Pad1)") (class "Default")
      (node (ref "RB01") (pin "1") (pinfunction "1_1") (pintype "passive"))
      (node (ref "SJB01") (pin "1") (pinfunction "1_1") (pintype "passive"))
      (node (ref "SV1") (pin "2") (pinfunction "2_2") (pintype "passive"))
    )
    (net (code "49") (name "SCL") (class "Default")
      (node (ref "IC801") (pin "23") (pinfunction "PF3_23") (pintype "bidirectional"))
      (node (ref "IC901B") (pin "3") (pinfunction "SCL_3") (pintype "input"))
      (node (ref "ICA01") (pin "2") (pinfunction "SCL_2") (pintype "input"))
      (node (ref "RN901") (pin "8") (pinfunction "2_8") (pintype "passive"))
      (node (ref "SV1") (pin "4") (pinfunction "4_4") (pintype "passive"))
      (node (ref "SV2") (pin "4") (pinfunction "4_4") (pintype "passive"))
      (node (ref "U$4") (pin "2") (pinfunction "SCL_2") (pintype "bidirectional"))
    )
    (net (code "50") (name "SDA") (class "Default")
      (node (ref "IC801") (pin "22") (pinfunction "PF2_22") (pintype "bidirectional"))
      (node (ref "IC901B") (pin "4") (pinfunction "SDA_4") (pintype "bidirectional"))
      (node (ref "ICA01") (pin "8") (pinfunction "SDA_8") (pintype "bidirectional"))
      (node (ref "RN901") (pin "7") (pinfunction "2_7") (pintype "passive"))
      (node (ref "SV1") (pin "3") (pinfunction "3_3") (pintype "passive"))
      (node (ref "SV2") (pin "3") (pinfunction "3_3") (pintype "passive"))
      (node (ref "U$4") (pin "1") (pinfunction "SDA_1") (pintype "bidirectional"))
    )
    (net (code "51") (name "unconnected-(CN601-Pad2)") (class "Default")
      (node (ref "CN601") (pin "2") (pinfunction "2_2") (pintype "passive"))
    )
    (net (code "52") (name "unconnected-(CN602-Pad4)") (class "Default")
      (node (ref "CN602") (pin "4") (pinfunction "4_4") (pintype "passive"))
    )
    (net (code "53") (name "unconnected-(IC801-PA5-Pad3)") (class "Default")
      (node (ref "IC801") (pin "3") (pinfunction "PA5_3") (pintype "bidirectional"))
    )
    (net (code "54") (name "unconnected-(IC801-PD1-Pad11)") (class "Default")
      (node (ref "IC801") (pin "11") (pinfunction "PD1_11") (pintype "bidirectional"))
    )
    (net (code "55") (name "unconnected-(IC801-PD3-Pad13)") (class "Default")
      (node (ref "IC801") (pin "13") (pinfunction "PD3_13") (pintype "bidirectional"))
    )
    (net (code "56") (name "unconnected-(IC901B-NC-Pad1)") (class "Default")
      (node (ref "IC901B") (pin "1") (pinfunction "NC_1") (pintype "no_connect"))
    )
    (net (code "57") (name "unconnected-(IC901B-NC-Pad6)") (class "Default")
      (node (ref "IC901B") (pin "6") (pinfunction "NC_6") (pintype "no_connect"))
    )
    (net (code "58") (name "unconnected-(ICC01-AD2{slash}DIO2-Pad29)") (class "Default")
      (node (ref "ICC01") (pin "29") (pinfunction "AD2/DIO2_29") (pintype "bidirectional"))
    )
    (net (code "59") (name "unconnected-(ICC01-AD3{slash}DIO3-Pad28)") (class "Default")
      (node (ref "ICC01") (pin "28") (pinfunction "AD3/DIO3_28") (pintype "bidirectional"))
    )
    (net (code "60") (name "unconnected-(ICC01-DIO4-Pad23)") (class "Default")
      (node (ref "ICC01") (pin "23") (pinfunction "DIO4_23") (pintype "bidirectional"))
    )
    (net (code "61") (name "unconnected-(ICC01-DIO12-Pad5)") (class "Default")
      (node (ref "ICC01") (pin "5") (pinfunction "DIO12_5") (pintype "bidirectional"))
    )
    (net (code "62") (name "unconnected-(ICC01-ON{slash}~{SLEEP}{slash}DIO9-Pad25)") (class "Default")
      (node (ref "ICC01") (pin "25") (pinfunction "ON/~{SLEEP}/DIO9_25") (pintype "bidirectional"))
    )
    (net (code "63") (name "unconnected-(ICC01-PWM1{slash}DIO11-Pad8)") (class "Default")
      (node (ref "ICC01") (pin "8") (pinfunction "PWM1/DIO11_8") (pintype "bidirectional"))
    )
    (net (code "64") (name "unconnected-(ICC01-RF-Pad33)") (class "Default")
      (node (ref "ICC01") (pin "33") (pinfunction "RF_33") (pintype "bidirectional"))
    )
    (net (code "65") (name "unconnected-(ICC01-RSSI_PWM{slash}DIO10-Pad7)") (class "Default")
      (node (ref "ICC01") (pin "7") (pinfunction "RSSI_PWM/DIO10_7") (pintype "bidirectional"))
    )
    (net (code "66") (name "unconnected-(ICC01-SPI_CLK{slash}DIO18-Pad13)") (class "Default")
      (node (ref "ICC01") (pin "13") (pinfunction "SPI_CLK/DIO18_13") (pintype "bidirectional"))
    )
    (net (code "67") (name "unconnected-(ICC01-SPI_MISO{slash}DIO15-Pad16)") (class "Default")
      (node (ref "ICC01") (pin "16") (pinfunction "SPI_MISO/DIO15_16") (pintype "bidirectional"))
    )
    (net (code "68") (name "unconnected-(ICC01-SPI_MOSI{slash}DIO16-Pad15)") (class "Default")
      (node (ref "ICC01") (pin "15") (pinfunction "SPI_MOSI/DIO16_15") (pintype "bidirectional"))
    )
    (net (code "69") (name "unconnected-(ICC01-SPI_~{ATTN}{slash}~{BOOTMODE}{slash}DIO19-Pad11)") (class "Default")
      (node (ref "ICC01") (pin "11") (pinfunction "SPI_~{ATTN}/~{BOOTMODE}/DIO19_11") (pintype "bidirectional"))
    )
    (net (code "70") (name "unconnected-(ICC01-SPI_~{SSEL}{slash}DIO17-Pad14)") (class "Default")
      (node (ref "ICC01") (pin "14") (pinfunction "SPI_~{SSEL}/DIO17_14") (pintype "bidirectional"))
    )
    (net (code "71") (name "unconnected-(ICC01-~{RESET}-Pad6)") (class "Default")
      (node (ref "ICC01") (pin "6") (pinfunction "~{RESET}_6") (pintype "input"))
    )
    (net (code "72") (name "unconnected-(J701-CDN-PadCD1)") (class "Default")
      (node (ref "J701") (pin "CD1") (pinfunction "CDN_CD1") (pintype "bidirectional"))
    )
    (net (code "73") (name "unconnected-(J701-DATA1-Pad8)") (class "Default")
      (node (ref "J701") (pin "8") (pinfunction "DATA1_8") (pintype "bidirectional"))
    )
    (net (code "74") (name "unconnected-(J701-DATA2-Pad1)") (class "Default")
      (node (ref "J701") (pin "1") (pinfunction "DATA2_1") (pintype "bidirectional"))
    )
    (net (code "75") (name "unconnected-(J701-G1-PadMP1)") (class "Default")
      (node (ref "J701") (pin "MP1") (pinfunction "G1_MP1") (pintype "bidirectional"))
    )
    (net (code "76") (name "unconnected-(J701-G2-PadMP2)") (class "Default")
      (node (ref "J701") (pin "MP2") (pinfunction "G2_MP2") (pintype "bidirectional"))
    )
    (net (code "77") (name "unconnected-(J701-G3-PadMP3)") (class "Default")
      (node (ref "J701") (pin "MP3") (pinfunction "G3_MP3") (pintype "bidirectional"))
    )
    (net (code "78") (name "unconnected-(J701-G4-PadMP4)") (class "Default")
      (node (ref "J701") (pin "MP4") (pinfunction "G4_MP4") (pintype "bidirectional"))
    )
    (net (code "79") (name "unconnected-(R603-Pad1)") (class "Default")
      (node (ref "R603") (pin "1") (pinfunction "1_1") (pintype "passive"))
    )
    (net (code "80") (name "unconnected-(SV1-Pad6)") (class "Default")
      (node (ref "SV1") (pin "6") (pinfunction "6_6") (pintype "passive"))
    )
    (net (code "81") (name "unconnected-(SV2-Pad2)") (class "Default")
      (node (ref "SV2") (pin "2") (pinfunction "2_2") (pintype "passive"))
    )
    (net (code "82") (name "unconnected-(SV2-Pad6)") (class "Default")
      (node (ref "SV2") (pin "6") (pinfunction "6_6") (pintype "passive"))
    )
    (net (code "83") (name "unconnected-(SW101-Pad1)") (class "Default")
      (node (ref "SW101") (pin "1") (pinfunction "1_1") (pintype "bidirectional"))
    )
    (net (code "84") (name "unconnected-(U$4-~{ALT}-Pad3)") (class "Default")
      (node (ref "U$4") (pin "3") (pinfunction "~{ALT}_3") (pintype "bidirectional"))
    )
  )
)
